# Nets_and_Buses.net
KiCad netlist of a schematic drawn in EasyEDA Pro
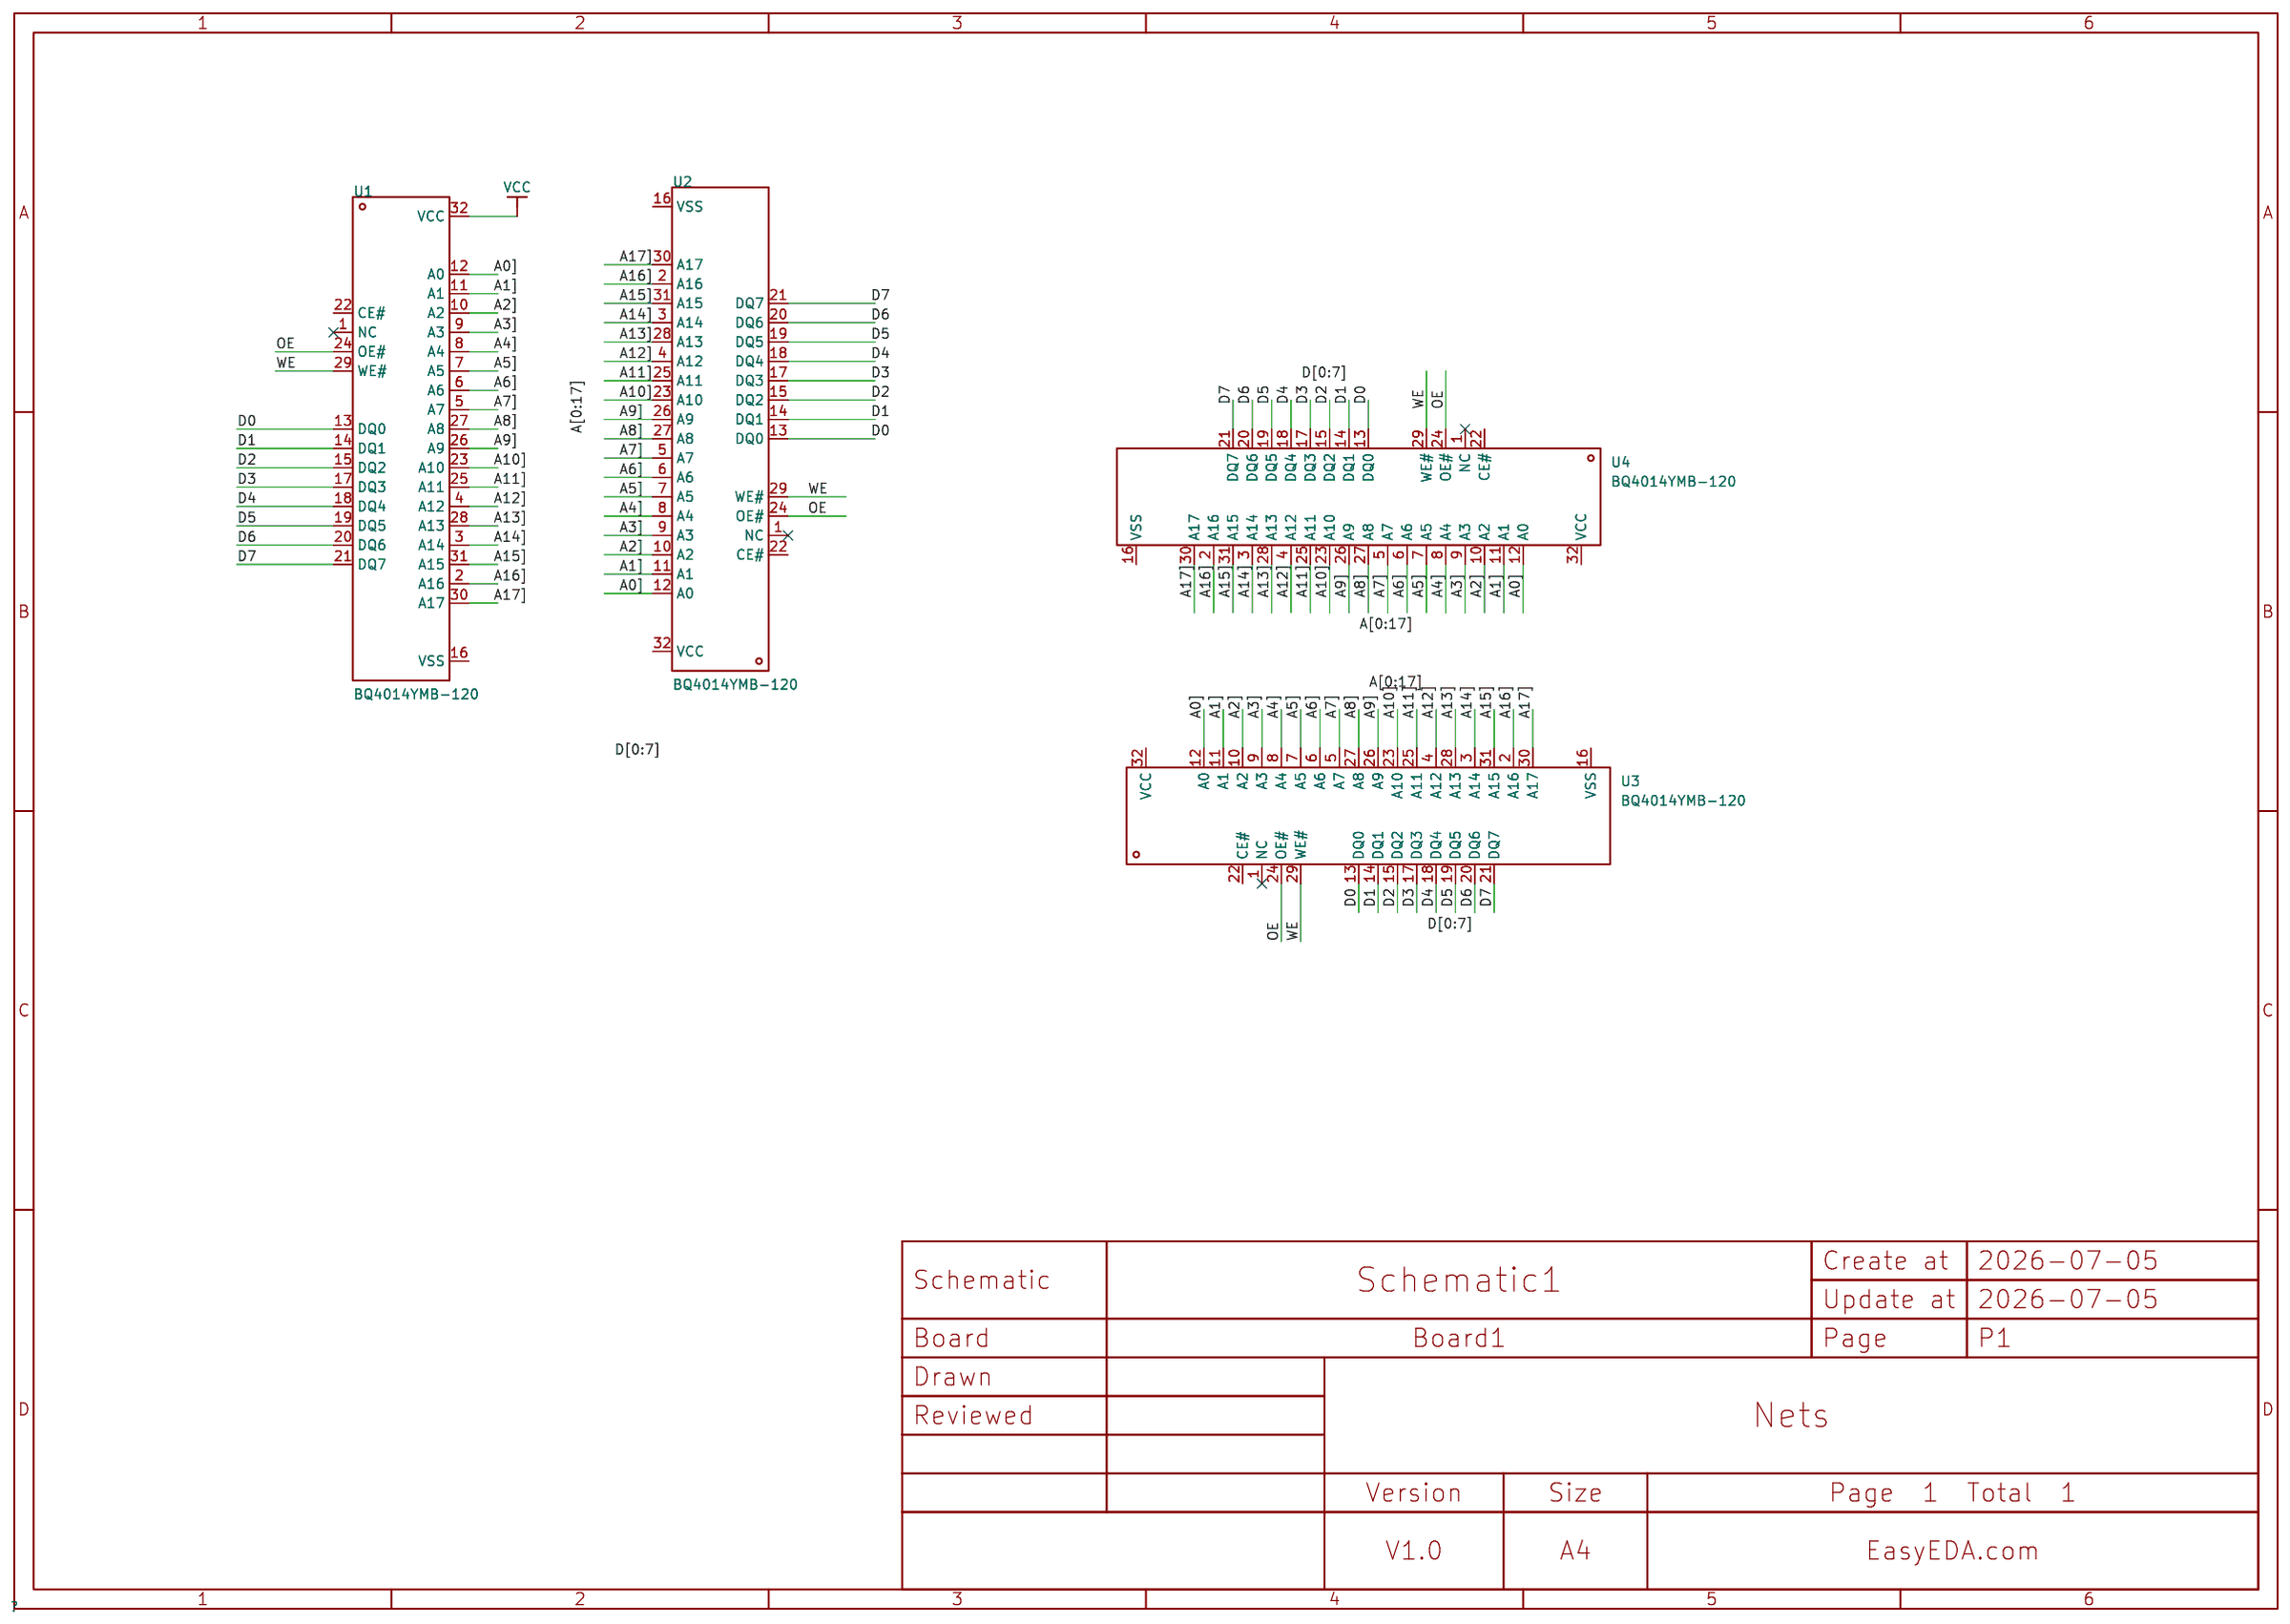
[diagram p0: schematic sheet]

(export (version "E")
  (design (tool "Eeschema 10.0.6"))
  (components
    (comp (ref "U1")
      (value "BQ4014YMB-120")
      (footprint "easyedapro:EDIP-32_L53.0-W18.8-P2.54-LS16.0-BL")
      (fields (field (name "Manufacturer") "TI(德州仪器)"))
      (libsource (lib "easyedapro") (part "BQ4014YMB-120"))
    )
    (comp (ref "U2")
      (value "BQ4014YMB-120")
      (footprint "easyedapro:EDIP-32_L53.0-W18.8-P2.54-LS16.0-BL")
      (fields (field (name "Manufacturer") "TI(德州仪器)"))
      (libsource (lib "easyedapro") (part "BQ4014YMB-120"))
    )
    (comp (ref "U3")
      (value "BQ4014YMB-120")
      (footprint "easyedapro:EDIP-32_L53.0-W18.8-P2.54-LS16.0-BL")
      (fields (field (name "Manufacturer") "TI(德州仪器)"))
      (libsource (lib "easyedapro") (part "BQ4014YMB-120"))
    )
    (comp (ref "U4")
      (value "BQ4014YMB-120")
      (footprint "easyedapro:EDIP-32_L53.0-W18.8-P2.54-LS16.0-BL")
      (fields (field (name "Manufacturer") "TI(德州仪器)"))
      (libsource (lib "easyedapro") (part "BQ4014YMB-120"))
    )
  )
  (nets
    (net (code "1") (name "/A0]") (class "Default")
      (node (ref "U1") (pin "12") (pinfunction "A0_12") (pintype "unspecified"))
      (node (ref "U2") (pin "12") (pinfunction "A0_12") (pintype "unspecified"))
      (node (ref "U3") (pin "12") (pinfunction "A0_12") (pintype "unspecified"))
      (node (ref "U4") (pin "12") (pinfunction "A0_12") (pintype "unspecified"))
    )
    (net (code "2") (name "/A1]") (class "Default")
      (node (ref "U1") (pin "11") (pinfunction "A1_11") (pintype "unspecified"))
      (node (ref "U2") (pin "11") (pinfunction "A1_11") (pintype "unspecified"))
      (node (ref "U3") (pin "11") (pinfunction "A1_11") (pintype "unspecified"))
      (node (ref "U4") (pin "11") (pinfunction "A1_11") (pintype "unspecified"))
    )
    (net (code "3") (name "/A2]") (class "Default")
      (node (ref "U1") (pin "10") (pinfunction "A2_10") (pintype "unspecified"))
      (node (ref "U2") (pin "10") (pinfunction "A2_10") (pintype "unspecified"))
      (node (ref "U3") (pin "10") (pinfunction "A2_10") (pintype "unspecified"))
      (node (ref "U4") (pin "10") (pinfunction "A2_10") (pintype "unspecified"))
    )
    (net (code "4") (name "/A3]") (class "Default")
      (node (ref "U1") (pin "9") (pinfunction "A3_9") (pintype "unspecified"))
      (node (ref "U2") (pin "9") (pinfunction "A3_9") (pintype "unspecified"))
      (node (ref "U3") (pin "9") (pinfunction "A3_9") (pintype "unspecified"))
      (node (ref "U4") (pin "9") (pinfunction "A3_9") (pintype "unspecified"))
    )
    (net (code "5") (name "/A4]") (class "Default")
      (node (ref "U1") (pin "8") (pinfunction "A4_8") (pintype "unspecified"))
      (node (ref "U2") (pin "8") (pinfunction "A4_8") (pintype "unspecified"))
      (node (ref "U3") (pin "8") (pinfunction "A4_8") (pintype "unspecified"))
      (node (ref "U4") (pin "8") (pinfunction "A4_8") (pintype "unspecified"))
    )
    (net (code "6") (name "/A5]") (class "Default")
      (node (ref "U1") (pin "7") (pinfunction "A5_7") (pintype "unspecified"))
      (node (ref "U2") (pin "7") (pinfunction "A5_7") (pintype "unspecified"))
      (node (ref "U3") (pin "7") (pinfunction "A5_7") (pintype "unspecified"))
      (node (ref "U4") (pin "7") (pinfunction "A5_7") (pintype "unspecified"))
    )
    (net (code "7") (name "/A6]") (class "Default")
      (node (ref "U1") (pin "6") (pinfunction "A6_6") (pintype "unspecified"))
      (node (ref "U2") (pin "6") (pinfunction "A6_6") (pintype "unspecified"))
      (node (ref "U3") (pin "6") (pinfunction "A6_6") (pintype "unspecified"))
      (node (ref "U4") (pin "6") (pinfunction "A6_6") (pintype "unspecified"))
    )
    (net (code "8") (name "/A7]") (class "Default")
      (node (ref "U1") (pin "5") (pinfunction "A7_5") (pintype "unspecified"))
      (node (ref "U2") (pin "5") (pinfunction "A7_5") (pintype "unspecified"))
      (node (ref "U3") (pin "5") (pinfunction "A7_5") (pintype "unspecified"))
      (node (ref "U4") (pin "5") (pinfunction "A7_5") (pintype "unspecified"))
    )
    (net (code "9") (name "/A8]") (class "Default")
      (node (ref "U1") (pin "27") (pinfunction "A8_27") (pintype "unspecified"))
      (node (ref "U2") (pin "27") (pinfunction "A8_27") (pintype "unspecified"))
      (node (ref "U3") (pin "27") (pinfunction "A8_27") (pintype "unspecified"))
      (node (ref "U4") (pin "27") (pinfunction "A8_27") (pintype "unspecified"))
    )
    (net (code "10") (name "/A9]") (class "Default")
      (node (ref "U1") (pin "26") (pinfunction "A9_26") (pintype "unspecified"))
      (node (ref "U2") (pin "26") (pinfunction "A9_26") (pintype "unspecified"))
      (node (ref "U3") (pin "26") (pinfunction "A9_26") (pintype "unspecified"))
      (node (ref "U4") (pin "26") (pinfunction "A9_26") (pintype "unspecified"))
    )
    (net (code "11") (name "/A10]") (class "Default")
      (node (ref "U1") (pin "23") (pinfunction "A10_23") (pintype "unspecified"))
      (node (ref "U2") (pin "23") (pinfunction "A10_23") (pintype "unspecified"))
      (node (ref "U3") (pin "23") (pinfunction "A10_23") (pintype "unspecified"))
      (node (ref "U4") (pin "23") (pinfunction "A10_23") (pintype "unspecified"))
    )
    (net (code "12") (name "/A11]") (class "Default")
      (node (ref "U1") (pin "25") (pinfunction "A11_25") (pintype "unspecified"))
      (node (ref "U2") (pin "25") (pinfunction "A11_25") (pintype "unspecified"))
      (node (ref "U3") (pin "25") (pinfunction "A11_25") (pintype "unspecified"))
      (node (ref "U4") (pin "25") (pinfunction "A11_25") (pintype "unspecified"))
    )
    (net (code "13") (name "/A12]") (class "Default")
      (node (ref "U1") (pin "4") (pinfunction "A12_4") (pintype "unspecified"))
      (node (ref "U2") (pin "4") (pinfunction "A12_4") (pintype "unspecified"))
      (node (ref "U3") (pin "4") (pinfunction "A12_4") (pintype "unspecified"))
      (node (ref "U4") (pin "4") (pinfunction "A12_4") (pintype "unspecified"))
    )
    (net (code "14") (name "/A13]") (class "Default")
      (node (ref "U1") (pin "28") (pinfunction "A13_28") (pintype "unspecified"))
      (node (ref "U2") (pin "28") (pinfunction "A13_28") (pintype "unspecified"))
      (node (ref "U3") (pin "28") (pinfunction "A13_28") (pintype "unspecified"))
      (node (ref "U4") (pin "28") (pinfunction "A13_28") (pintype "unspecified"))
    )
    (net (code "15") (name "/A14]") (class "Default")
      (node (ref "U1") (pin "3") (pinfunction "A14_3") (pintype "unspecified"))
      (node (ref "U2") (pin "3") (pinfunction "A14_3") (pintype "unspecified"))
      (node (ref "U3") (pin "3") (pinfunction "A14_3") (pintype "unspecified"))
      (node (ref "U4") (pin "3") (pinfunction "A14_3") (pintype "unspecified"))
    )
    (net (code "16") (name "/A15]") (class "Default")
      (node (ref "U1") (pin "31") (pinfunction "A15_31") (pintype "unspecified"))
      (node (ref "U2") (pin "31") (pinfunction "A15_31") (pintype "unspecified"))
      (node (ref "U3") (pin "31") (pinfunction "A15_31") (pintype "unspecified"))
      (node (ref "U4") (pin "31") (pinfunction "A15_31") (pintype "unspecified"))
    )
    (net (code "17") (name "/A16]") (class "Default")
      (node (ref "U1") (pin "2") (pinfunction "A16_2") (pintype "unspecified"))
      (node (ref "U2") (pin "2") (pinfunction "A16_2") (pintype "unspecified"))
      (node (ref "U3") (pin "2") (pinfunction "A16_2") (pintype "unspecified"))
      (node (ref "U4") (pin "2") (pinfunction "A16_2") (pintype "unspecified"))
    )
    (net (code "18") (name "/A17]") (class "Default")
      (node (ref "U1") (pin "30") (pinfunction "A17_30") (pintype "unspecified"))
      (node (ref "U2") (pin "30") (pinfunction "A17_30") (pintype "unspecified"))
      (node (ref "U3") (pin "30") (pinfunction "A17_30") (pintype "unspecified"))
      (node (ref "U4") (pin "30") (pinfunction "A17_30") (pintype "unspecified"))
    )
    (net (code "20") (name "/D0") (class "Default")
      (node (ref "U1") (pin "13") (pinfunction "DQ0_13") (pintype "unspecified"))
      (node (ref "U2") (pin "13") (pinfunction "DQ0_13") (pintype "unspecified"))
      (node (ref "U3") (pin "13") (pinfunction "DQ0_13") (pintype "unspecified"))
      (node (ref "U4") (pin "13") (pinfunction "DQ0_13") (pintype "unspecified"))
    )
    (net (code "21") (name "/D1") (class "Default")
      (node (ref "U1") (pin "14") (pinfunction "DQ1_14") (pintype "unspecified"))
      (node (ref "U2") (pin "14") (pinfunction "DQ1_14") (pintype "unspecified"))
      (node (ref "U3") (pin "14") (pinfunction "DQ1_14") (pintype "unspecified"))
      (node (ref "U4") (pin "14") (pinfunction "DQ1_14") (pintype "unspecified"))
    )
    (net (code "22") (name "/D2") (class "Default")
      (node (ref "U1") (pin "15") (pinfunction "DQ2_15") (pintype "unspecified"))
      (node (ref "U2") (pin "15") (pinfunction "DQ2_15") (pintype "unspecified"))
      (node (ref "U3") (pin "15") (pinfunction "DQ2_15") (pintype "unspecified"))
      (node (ref "U4") (pin "15") (pinfunction "DQ2_15") (pintype "unspecified"))
    )
    (net (code "23") (name "/D3") (class "Default")
      (node (ref "U1") (pin "17") (pinfunction "DQ3_17") (pintype "unspecified"))
      (node (ref "U2") (pin "17") (pinfunction "DQ3_17") (pintype "unspecified"))
      (node (ref "U3") (pin "17") (pinfunction "DQ3_17") (pintype "unspecified"))
      (node (ref "U4") (pin "17") (pinfunction "DQ3_17") (pintype "unspecified"))
    )
    (net (code "24") (name "/D4") (class "Default")
      (node (ref "U1") (pin "18") (pinfunction "DQ4_18") (pintype "unspecified"))
      (node (ref "U2") (pin "18") (pinfunction "DQ4_18") (pintype "unspecified"))
      (node (ref "U3") (pin "18") (pinfunction "DQ4_18") (pintype "unspecified"))
      (node (ref "U4") (pin "18") (pinfunction "DQ4_18") (pintype "unspecified"))
    )
    (net (code "25") (name "/D5") (class "Default")
      (node (ref "U1") (pin "19") (pinfunction "DQ5_19") (pintype "unspecified"))
      (node (ref "U2") (pin "19") (pinfunction "DQ5_19") (pintype "unspecified"))
      (node (ref "U3") (pin "19") (pinfunction "DQ5_19") (pintype "unspecified"))
      (node (ref "U4") (pin "19") (pinfunction "DQ5_19") (pintype "unspecified"))
    )
    (net (code "26") (name "/D6") (class "Default")
      (node (ref "U1") (pin "20") (pinfunction "DQ6_20") (pintype "unspecified"))
      (node (ref "U2") (pin "20") (pinfunction "DQ6_20") (pintype "unspecified"))
      (node (ref "U3") (pin "20") (pinfunction "DQ6_20") (pintype "unspecified"))
      (node (ref "U4") (pin "20") (pinfunction "DQ6_20") (pintype "unspecified"))
    )
    (net (code "27") (name "/D7") (class "Default")
      (node (ref "U1") (pin "21") (pinfunction "DQ7_21") (pintype "unspecified"))
      (node (ref "U2") (pin "21") (pinfunction "DQ7_21") (pintype "unspecified"))
      (node (ref "U3") (pin "21") (pinfunction "DQ7_21") (pintype "unspecified"))
      (node (ref "U4") (pin "21") (pinfunction "DQ7_21") (pintype "unspecified"))
    )
    (net (code "29") (name "/OE") (class "Default")
      (node (ref "U1") (pin "24") (pinfunction "OE#_24") (pintype "unspecified"))
      (node (ref "U2") (pin "24") (pinfunction "OE#_24") (pintype "unspecified"))
      (node (ref "U3") (pin "24") (pinfunction "OE#_24") (pintype "unspecified"))
      (node (ref "U4") (pin "24") (pinfunction "OE#_24") (pintype "unspecified"))
    )
    (net (code "30") (name "/WE") (class "Default")
      (node (ref "U1") (pin "29") (pinfunction "WE#_29") (pintype "unspecified"))
      (node (ref "U2") (pin "29") (pinfunction "WE#_29") (pintype "unspecified"))
      (node (ref "U3") (pin "29") (pinfunction "WE#_29") (pintype "unspecified"))
      (node (ref "U4") (pin "29") (pinfunction "WE#_29") (pintype "unspecified"))
    )
    (net (code "31") (name "VCC") (class "Default")
      (node (ref "U1") (pin "32") (pinfunction "VCC_32") (pintype "unspecified"))
    )
    (net (code "32") (name "unconnected-(U1-CE#-Pad22)") (class "Default")
      (node (ref "U1") (pin "22") (pinfunction "CE#_22") (pintype "unspecified"))
    )
    (net (code "33") (name "unconnected-(U1-NC-Pad1)") (class "Default")
      (node (ref "U1") (pin "1") (pinfunction "NC_1") (pintype "unspecified+no_connect"))
    )
    (net (code "34") (name "unconnected-(U1-VSS-Pad16)") (class "Default")
      (node (ref "U1") (pin "16") (pinfunction "VSS_16") (pintype "unspecified"))
    )
    (net (code "35") (name "unconnected-(U2-CE#-Pad22)") (class "Default")
      (node (ref "U2") (pin "22") (pinfunction "CE#_22") (pintype "unspecified"))
    )
    (net (code "36") (name "unconnected-(U2-NC-Pad1)") (class "Default")
      (node (ref "U2") (pin "1") (pinfunction "NC_1") (pintype "unspecified+no_connect"))
    )
    (net (code "37") (name "unconnected-(U2-VCC-Pad32)") (class "Default")
      (node (ref "U2") (pin "32") (pinfunction "VCC_32") (pintype "unspecified"))
    )
    (net (code "38") (name "unconnected-(U2-VSS-Pad16)") (class "Default")
      (node (ref "U2") (pin "16") (pinfunction "VSS_16") (pintype "unspecified"))
    )
    (net (code "39") (name "unconnected-(U3-CE#-Pad22)") (class "Default")
      (node (ref "U3") (pin "22") (pinfunction "CE#_22") (pintype "unspecified"))
    )
    (net (code "40") (name "unconnected-(U3-NC-Pad1)") (class "Default")
      (node (ref "U3") (pin "1") (pinfunction "NC_1") (pintype "unspecified+no_connect"))
    )
    (net (code "41") (name "unconnected-(U3-VCC-Pad32)") (class "Default")
      (node (ref "U3") (pin "32") (pinfunction "VCC_32") (pintype "unspecified"))
    )
    (net (code "42") (name "unconnected-(U3-VSS-Pad16)") (class "Default")
      (node (ref "U3") (pin "16") (pinfunction "VSS_16") (pintype "unspecified"))
    )
    (net (code "43") (name "unconnected-(U4-CE#-Pad22)") (class "Default")
      (node (ref "U4") (pin "22") (pinfunction "CE#_22") (pintype "unspecified"))
    )
    (net (code "44") (name "unconnected-(U4-NC-Pad1)") (class "Default")
      (node (ref "U4") (pin "1") (pinfunction "NC_1") (pintype "unspecified+no_connect"))
    )
    (net (code "45") (name "unconnected-(U4-VCC-Pad32)") (class "Default")
      (node (ref "U4") (pin "32") (pinfunction "VCC_32") (pintype "unspecified"))
    )
    (net (code "46") (name "unconnected-(U4-VSS-Pad16)") (class "Default")
      (node (ref "U4") (pin "16") (pinfunction "VSS_16") (pintype "unspecified"))
    )
  )
)
